# LB_BIT_i32_filter-v03_5_6.net
KiCad netlist of a schematic drawn in EAGLE
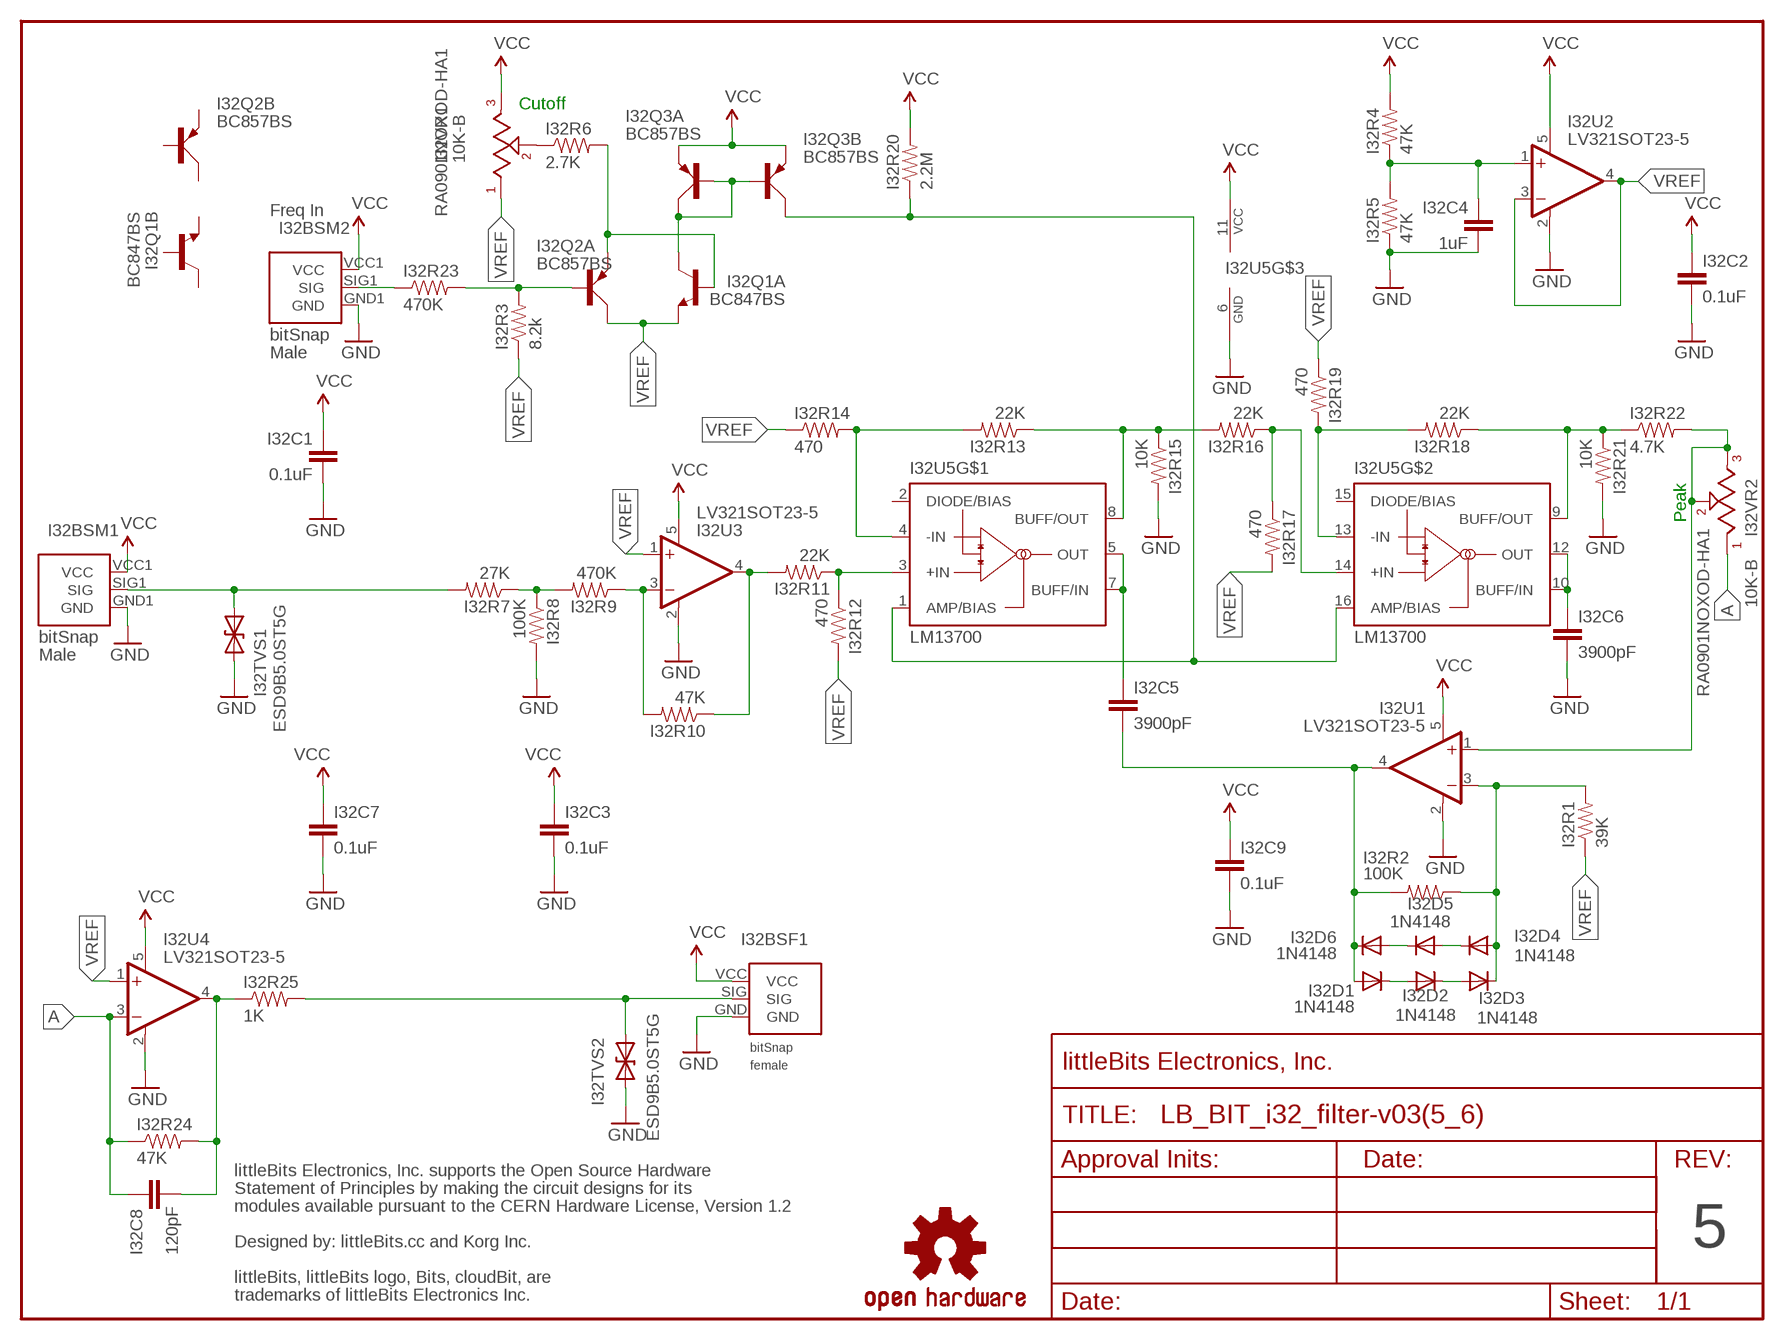
[diagram p0: schematic, sheet 1]

(export (version "E")
  (design (tool "Eeschema 10.0.6"))
  (components
    (comp (ref "I32BSF1")
      (value "BITSNAP_V03_FEMALE")
      (footprint "eagle-import:BITSNAP_V03_FEMALE")
      (libsource (lib "eagle-import") (part "BITSNAP_V03_FEMALE"))
    )
    (comp (ref "I32BSM1")
      (value "BITSNAP_V03_MALE")
      (footprint "eagle-import:BITSNAP_V03_MALE")
      (libsource (lib "eagle-import") (part "BITSNAP_V03_MALE"))
    )
    (comp (ref "I32BSM2")
      (value "BITSNAP_V03_MALE")
      (footprint "eagle-import:BITSNAP_V03_MALE")
      (libsource (lib "eagle-import") (part "BITSNAP_V03_MALE"))
    )
    (comp (ref "I32C1")
      (value "0.1uF")
      (footprint "eagle-import:CAP-0603")
      (libsource (lib "eagle-import") (part "CAPCAP-0603"))
    )
    (comp (ref "I32C2")
      (value "0.1uF")
      (footprint "eagle-import:CAP-0603")
      (libsource (lib "eagle-import") (part "CAPCAP-0603"))
    )
    (comp (ref "I32C3")
      (value "0.1uF")
      (footprint "eagle-import:CAP-0603")
      (libsource (lib "eagle-import") (part "CAPCAP-0603"))
    )
    (comp (ref "I32C4")
      (value "1uF")
      (footprint "eagle-import:CAP-0603")
      (libsource (lib "eagle-import") (part "CAPCAP-0603"))
    )
    (comp (ref "I32C5")
      (value "3900pF")
      (footprint "eagle-import:CAP-0603")
      (libsource (lib "eagle-import") (part "CAPCAP-0603"))
    )
    (comp (ref "I32C6")
      (value "3900pF")
      (footprint "eagle-import:CAP-0603")
      (libsource (lib "eagle-import") (part "CAPCAP-0603"))
    )
    (comp (ref "I32C7")
      (value "0.1uF")
      (footprint "eagle-import:CAP-0603")
      (libsource (lib "eagle-import") (part "CAPCAP-0603"))
    )
    (comp (ref "I32C8")
      (value "120pF")
      (footprint "eagle-import:CAP-0603")
      (libsource (lib "eagle-import") (part "CAPCAP-0603"))
    )
    (comp (ref "I32C9")
      (value "0.1uF")
      (footprint "eagle-import:CAP-0603")
      (libsource (lib "eagle-import") (part "CAPCAP-0603"))
    )
    (comp (ref "I32D1")
      (value "1N4148")
      (footprint "eagle-import:SOD-323")
      (libsource (lib "eagle-import") (part "DIODESOD"))
    )
    (comp (ref "I32D2")
      (value "1N4148")
      (footprint "eagle-import:SOD-323")
      (libsource (lib "eagle-import") (part "DIODESOD"))
    )
    (comp (ref "I32D3")
      (value "1N4148")
      (footprint "eagle-import:SOD-323")
      (libsource (lib "eagle-import") (part "DIODESOD"))
    )
    (comp (ref "I32D4")
      (value "1N4148")
      (footprint "eagle-import:SOD-323")
      (libsource (lib "eagle-import") (part "DIODESOD"))
    )
    (comp (ref "I32D5")
      (value "1N4148")
      (footprint "eagle-import:SOD-323")
      (libsource (lib "eagle-import") (part "DIODESOD"))
    )
    (comp (ref "I32D6")
      (value "1N4148")
      (footprint "eagle-import:SOD-323")
      (libsource (lib "eagle-import") (part "DIODESOD"))
    )
    (comp (ref "I32Q1")
      (value "BC847BS")
      (footprint "eagle-import:SOT-363_PHILLIPS")
      (libsource (lib "eagle-import") (part "TRANS-BJT_NPN-DUAL-BC847BS"))
    )
    (comp (ref "I32Q2")
      (value "BC857BS")
      (footprint "eagle-import:SOT-363_PHILLIPS")
      (libsource (lib "eagle-import") (part "TRANS-BJT_PNP-DUALBC857"))
    )
    (comp (ref "I32Q3")
      (value "BC857BS")
      (footprint "eagle-import:SOT-363_PHILLIPS")
      (libsource (lib "eagle-import") (part "TRANS-BJT_PNP-DUALBC857"))
    )
    (comp (ref "I32R1")
      (value "39K")
      (footprint "eagle-import:RES-0603")
      (libsource (lib "eagle-import") (part "RESISTOR0603"))
    )
    (comp (ref "I32R2")
      (value "100K")
      (footprint "eagle-import:RES-0603")
      (libsource (lib "eagle-import") (part "RESISTOR0603"))
    )
    (comp (ref "I32R3")
      (value "8.2k")
      (footprint "eagle-import:RES-0603")
      (libsource (lib "eagle-import") (part "RESISTOR0603"))
    )
    (comp (ref "I32R4")
      (value "47K")
      (footprint "eagle-import:RES-0603")
      (libsource (lib "eagle-import") (part "RESISTOR0603"))
    )
    (comp (ref "I32R5")
      (value "47K")
      (footprint "eagle-import:RES-0603")
      (libsource (lib "eagle-import") (part "RESISTOR0603"))
    )
    (comp (ref "I32R6")
      (value "2.7K")
      (footprint "eagle-import:RES-0603")
      (libsource (lib "eagle-import") (part "RESISTOR0603"))
    )
    (comp (ref "I32R7")
      (value "27K")
      (footprint "eagle-import:RES-0603")
      (libsource (lib "eagle-import") (part "RESISTOR0603"))
    )
    (comp (ref "I32R8")
      (value "100K")
      (footprint "eagle-import:RES-0603")
      (libsource (lib "eagle-import") (part "RESISTOR0603"))
    )
    (comp (ref "I32R9")
      (value "470K")
      (footprint "eagle-import:RES-0603")
      (libsource (lib "eagle-import") (part "RESISTOR0603"))
    )
    (comp (ref "I32R10")
      (value "47K")
      (footprint "eagle-import:RES-0603")
      (libsource (lib "eagle-import") (part "RESISTOR0603"))
    )
    (comp (ref "I32R11")
      (value "22K")
      (footprint "eagle-import:RES-0603")
      (libsource (lib "eagle-import") (part "RESISTOR0603"))
    )
    (comp (ref "I32R12")
      (value "470")
      (footprint "eagle-import:RES-0603")
      (libsource (lib "eagle-import") (part "RESISTOR0603"))
    )
    (comp (ref "I32R13")
      (value "22K")
      (footprint "eagle-import:RES-0603")
      (libsource (lib "eagle-import") (part "RESISTOR0603"))
    )
    (comp (ref "I32R14")
      (value "470")
      (footprint "eagle-import:RES-0603")
      (libsource (lib "eagle-import") (part "RESISTOR0603"))
    )
    (comp (ref "I32R15")
      (value "10K")
      (footprint "eagle-import:RES-0603")
      (libsource (lib "eagle-import") (part "RESISTOR0603"))
    )
    (comp (ref "I32R16")
      (value "22K")
      (footprint "eagle-import:RES-0603")
      (libsource (lib "eagle-import") (part "RESISTOR0603"))
    )
    (comp (ref "I32R17")
      (value "470")
      (footprint "eagle-import:RES-0603")
      (libsource (lib "eagle-import") (part "RESISTOR0603"))
    )
    (comp (ref "I32R18")
      (value "22K")
      (footprint "eagle-import:RES-0603")
      (libsource (lib "eagle-import") (part "RESISTOR0603"))
    )
    (comp (ref "I32R19")
      (value "470")
      (footprint "eagle-import:RES-0603")
      (libsource (lib "eagle-import") (part "RESISTOR0603"))
    )
    (comp (ref "I32R20")
      (value "2.2M")
      (footprint "eagle-import:RES-0603")
      (libsource (lib "eagle-import") (part "RESISTOR0603"))
    )
    (comp (ref "I32R21")
      (value "10K")
      (footprint "eagle-import:RES-0603")
      (libsource (lib "eagle-import") (part "RESISTOR0603"))
    )
    (comp (ref "I32R22")
      (value "4.7K")
      (footprint "eagle-import:RES-0603")
      (libsource (lib "eagle-import") (part "RESISTOR0603"))
    )
    (comp (ref "I32R23")
      (value "470K")
      (footprint "eagle-import:RES-0603")
      (libsource (lib "eagle-import") (part "RESISTOR0603"))
    )
    (comp (ref "I32R24")
      (value "47K")
      (footprint "eagle-import:RES-0603")
      (libsource (lib "eagle-import") (part "RESISTOR0603"))
    )
    (comp (ref "I32R25")
      (value "1K")
      (footprint "eagle-import:RES-0603")
      (libsource (lib "eagle-import") (part "RESISTOR0603"))
    )
    (comp (ref "I32TVS1")
      (value "ESD9B5.0ST5G")
      (footprint "eagle-import:SOD-923")
      (libsource (lib "eagle-import") (part "DIODE-TVSSOD-923"))
    )
    (comp (ref "I32TVS2")
      (value "ESD9B5.0ST5G")
      (footprint "eagle-import:SOD-923")
      (libsource (lib "eagle-import") (part "DIODE-TVSSOD-923"))
    )
    (comp (ref "I32U1")
      (value "LV321SOT23-5")
      (footprint "eagle-import:SOT23-5")
      (libsource (lib "eagle-import") (part "LV321SOT23-5"))
    )
    (comp (ref "I32U2")
      (value "LV321SOT23-5")
      (footprint "eagle-import:SOT23-5")
      (libsource (lib "eagle-import") (part "LV321SOT23-5"))
    )
    (comp (ref "I32U3")
      (value "LV321SOT23-5")
      (footprint "eagle-import:SOT23-5")
      (libsource (lib "eagle-import") (part "LV321SOT23-5"))
    )
    (comp (ref "I32U4")
      (value "LV321SOT23-5")
      (footprint "eagle-import:SOT23-5")
      (libsource (lib "eagle-import") (part "LV321SOT23-5"))
    )
    (comp (ref "I32U5")
      (value "LM13700")
      (footprint "eagle-import:DMP16")
      (libsource (lib "eagle-import") (part "XX-13700DMP16"))
    )
    (comp (ref "I32VR1")
      (value "10K-B")
      (footprint "eagle-import:ALPS_POT")
      (libsource (lib "eagle-import") (part "ALPS_POTTH"))
    )
    (comp (ref "I32VR2")
      (value "10K-B")
      (footprint "eagle-import:ALPS_POT")
      (libsource (lib "eagle-import") (part "ALPS_POTTH"))
    )
    (comp (ref "U$1")
      (value "FRAME-LETTER-OHWOHW")
      (footprint "eagle-import:FABDWG01-OHW")
      (libsource (lib "eagle-import") (part "FRAME-LETTER-OHWOHW"))
    )
    (comp (ref "U$2")
      (value "OSHWCREDIT-KORG")
      (footprint "eagle-import:OSHWCREDIT-KORG")
      (libsource (lib "eagle-import") (part "OSHWCREDIT-KORG"))
    )
    (comp (ref "U$3")
      (value "OSHW-LOGOL")
      (footprint "eagle-import:OSHW-LOGO-L")
      (libsource (lib "eagle-import") (part "OSHW-LOGOL"))
    )
  )
  (nets
    (net (code "1") (name "A") (class "Default")
      (node (ref "I32C8") (pin "1") (pinfunction "1_1") (pintype "passive"))
      (node (ref "I32R24") (pin "1") (pinfunction "1_1") (pintype "passive"))
      (node (ref "I32U4") (pin "3") (pinfunction "-IN_3") (pintype "input"))
      (node (ref "I32VR2") (pin "1") (pinfunction "1_1") (pintype "passive"))
    )
    (net (code "2") (name "GND") (class "Default")
      (node (ref "I32BSF1") (pin "GND") (pinfunction "GND_GND") (pintype "bidirectional"))
      (node (ref "I32BSM1") (pin "GND1") (pinfunction "GND_GND1") (pintype "bidirectional"))
      (node (ref "I32BSM2") (pin "GND1") (pinfunction "GND_GND1") (pintype "bidirectional"))
      (node (ref "I32C1") (pin "2") (pinfunction "2_2") (pintype "passive"))
      (node (ref "I32C2") (pin "2") (pinfunction "2_2") (pintype "passive"))
      (node (ref "I32C3") (pin "2") (pinfunction "2_2") (pintype "passive"))
      (node (ref "I32C4") (pin "2") (pinfunction "2_2") (pintype "passive"))
      (node (ref "I32C6") (pin "2") (pinfunction "2_2") (pintype "passive"))
      (node (ref "I32C7") (pin "2") (pinfunction "2_2") (pintype "passive"))
      (node (ref "I32C9") (pin "2") (pinfunction "2_2") (pintype "passive"))
      (node (ref "I32R15") (pin "2") (pinfunction "2_2") (pintype "passive"))
      (node (ref "I32R21") (pin "2") (pinfunction "2_2") (pintype "passive"))
      (node (ref "I32R5") (pin "1") (pinfunction "1_1") (pintype "passive"))
      (node (ref "I32R8") (pin "2") (pinfunction "2_2") (pintype "passive"))
      (node (ref "I32TVS1") (pin "1") (pinfunction "A_1") (pintype "passive"))
      (node (ref "I32TVS2") (pin "1") (pinfunction "A_1") (pintype "passive"))
      (node (ref "I32U1") (pin "2") (pinfunction "V-_2") (pintype "power_in"))
      (node (ref "I32U2") (pin "2") (pinfunction "V-_2") (pintype "power_in"))
      (node (ref "I32U3") (pin "2") (pinfunction "V-_2") (pintype "power_in"))
      (node (ref "I32U4") (pin "2") (pinfunction "V-_2") (pintype "power_in"))
      (node (ref "I32U5") (pin "6") (pinfunction "GND_6") (pintype "power_in"))
    )
    (net (code "3") (name "Net-(I32BSM1-SIG)") (class "Default")
      (node (ref "I32BSM1") (pin "SIG1") (pinfunction "SIG_SIG1") (pintype "bidirectional"))
      (node (ref "I32R7") (pin "2") (pinfunction "2_2") (pintype "passive"))
      (node (ref "I32TVS1") (pin "2") (pinfunction "C_2") (pintype "passive"))
    )
    (net (code "4") (name "Net-(I32BSM2-SIG)") (class "Default")
      (node (ref "I32BSM2") (pin "SIG1") (pinfunction "SIG_SIG1") (pintype "bidirectional"))
      (node (ref "I32R23") (pin "1") (pinfunction "1_1") (pintype "passive"))
    )
    (net (code "5") (name "Net-(I32D1-A)") (class "Default")
      (node (ref "I32C5") (pin "2") (pinfunction "2_2") (pintype "passive"))
      (node (ref "I32D1") (pin "2") (pinfunction "A_2") (pintype "passive"))
      (node (ref "I32D6") (pin "1") (pinfunction "C_1") (pintype "passive"))
      (node (ref "I32R2") (pin "2") (pinfunction "2_2") (pintype "passive"))
      (node (ref "I32U1") (pin "4") (pinfunction "OUT_4") (pintype "output"))
    )
    (net (code "6") (name "Net-(I32D1-C)") (class "Default")
      (node (ref "I32D1") (pin "1") (pinfunction "C_1") (pintype "passive"))
      (node (ref "I32D2") (pin "2") (pinfunction "A_2") (pintype "passive"))
    )
    (net (code "7") (name "Net-(I32D2-C)") (class "Default")
      (node (ref "I32D2") (pin "1") (pinfunction "C_1") (pintype "passive"))
      (node (ref "I32D3") (pin "2") (pinfunction "A_2") (pintype "passive"))
    )
    (net (code "8") (name "Net-(I32D3-C)") (class "Default")
      (node (ref "I32D3") (pin "1") (pinfunction "C_1") (pintype "passive"))
      (node (ref "I32D4") (pin "2") (pinfunction "A_2") (pintype "passive"))
      (node (ref "I32R1") (pin "2") (pinfunction "2_2") (pintype "passive"))
      (node (ref "I32R2") (pin "1") (pinfunction "1_1") (pintype "passive"))
      (node (ref "I32U1") (pin "3") (pinfunction "-IN_3") (pintype "input"))
    )
    (net (code "9") (name "Net-(I32D4-C)") (class "Default")
      (node (ref "I32D4") (pin "1") (pinfunction "C_1") (pintype "passive"))
      (node (ref "I32D5") (pin "2") (pinfunction "A_2") (pintype "passive"))
    )
    (net (code "10") (name "Net-(I32D5-C)") (class "Default")
      (node (ref "I32D5") (pin "1") (pinfunction "C_1") (pintype "passive"))
      (node (ref "I32D6") (pin "2") (pinfunction "A_2") (pintype "passive"))
    )
    (net (code "11") (name "Net-(I32Q1A-B)") (class "Default")
      (node (ref "I32Q1") (pin "2") (pinfunction "B_2") (pintype "passive"))
      (node (ref "I32Q2") (pin "1") (pinfunction "E_1") (pintype "passive"))
      (node (ref "I32R6") (pin "2") (pinfunction "2_2") (pintype "passive"))
    )
    (net (code "12") (name "Net-(I32Q1A-C)") (class "Default")
      (node (ref "I32Q1") (pin "6") (pinfunction "C_6") (pintype "passive"))
      (node (ref "I32Q3") (pin "2") (pinfunction "B_2") (pintype "passive"))
      (node (ref "I32Q3") (pin "5") (pinfunction "B_5") (pintype "passive"))
      (node (ref "I32Q3") (pin "6") (pinfunction "C_6") (pintype "passive"))
    )
    (net (code "13") (name "Net-(I32Q2A-B)") (class "Default")
      (node (ref "I32Q2") (pin "2") (pinfunction "B_2") (pintype "passive"))
      (node (ref "I32R23") (pin "2") (pinfunction "2_2") (pintype "passive"))
      (node (ref "I32R3") (pin "2") (pinfunction "2_2") (pintype "passive"))
    )
    (net (code "14") (name "Net-(I32Q3B-C)") (class "Default")
      (node (ref "I32Q3") (pin "3") (pinfunction "C_3") (pintype "passive"))
      (node (ref "I32R20") (pin "1") (pinfunction "1_1") (pintype "passive"))
      (node (ref "I32U5") (pin "1") (pinfunction "AMP/BIAS_1") (pintype "passive"))
      (node (ref "I32U5") (pin "16") (pinfunction "AMP/BIAS_16") (pintype "passive"))
    )
    (net (code "15") (name "Net-(I32R6-Pad1)") (class "Default")
      (node (ref "I32R6") (pin "1") (pinfunction "1_1") (pintype "passive"))
      (node (ref "I32VR1") (pin "2") (pinfunction "2_2") (pintype "passive"))
    )
    (net (code "16") (name "Net-(I32R7-Pad1)") (class "Default")
      (node (ref "I32R7") (pin "1") (pinfunction "1_1") (pintype "passive"))
      (node (ref "I32R8") (pin "1") (pinfunction "1_1") (pintype "passive"))
      (node (ref "I32R9") (pin "2") (pinfunction "2_2") (pintype "passive"))
    )
    (net (code "17") (name "Net-(I32TVS2-C)") (class "Default")
      (node (ref "I32BSF1") (pin "SIG") (pinfunction "SIG_SIG") (pintype "bidirectional"))
      (node (ref "I32R25") (pin "2") (pinfunction "2_2") (pintype "passive"))
      (node (ref "I32TVS2") (pin "2") (pinfunction "C_2") (pintype "passive"))
    )
    (net (code "18") (name "Net-(I32U1-+IN)") (class "Default")
      (node (ref "I32R22") (pin "2") (pinfunction "2_2") (pintype "passive"))
      (node (ref "I32U1") (pin "1") (pinfunction "+IN_1") (pintype "input"))
      (node (ref "I32VR2") (pin "2") (pinfunction "2_2") (pintype "passive"))
      (node (ref "I32VR2") (pin "3") (pinfunction "3_3") (pintype "passive"))
    )
    (net (code "19") (name "Net-(I32U2-+IN)") (class "Default")
      (node (ref "I32C4") (pin "1") (pinfunction "1_1") (pintype "passive"))
      (node (ref "I32R4") (pin "1") (pinfunction "1_1") (pintype "passive"))
      (node (ref "I32R5") (pin "2") (pinfunction "2_2") (pintype "passive"))
      (node (ref "I32U2") (pin "1") (pinfunction "+IN_1") (pintype "input"))
    )
    (net (code "20") (name "Net-(I32U3--IN)") (class "Default")
      (node (ref "I32R10") (pin "2") (pinfunction "2_2") (pintype "passive"))
      (node (ref "I32R9") (pin "1") (pinfunction "1_1") (pintype "passive"))
      (node (ref "I32U3") (pin "3") (pinfunction "-IN_3") (pintype "input"))
    )
    (net (code "21") (name "Net-(I32U3-OUT)") (class "Default")
      (node (ref "I32R10") (pin "1") (pinfunction "1_1") (pintype "passive"))
      (node (ref "I32R11") (pin "2") (pinfunction "2_2") (pintype "passive"))
      (node (ref "I32U3") (pin "4") (pinfunction "OUT_4") (pintype "output"))
    )
    (net (code "22") (name "Net-(I32U4-OUT)") (class "Default")
      (node (ref "I32C8") (pin "2") (pinfunction "2_2") (pintype "passive"))
      (node (ref "I32R24") (pin "2") (pinfunction "2_2") (pintype "passive"))
      (node (ref "I32R25") (pin "1") (pinfunction "1_1") (pintype "passive"))
      (node (ref "I32U4") (pin "4") (pinfunction "OUT_4") (pintype "output"))
    )
    (net (code "23") (name "Net-(I32U5A-+IN)") (class "Default")
      (node (ref "I32R11") (pin "1") (pinfunction "1_1") (pintype "passive"))
      (node (ref "I32R12") (pin "1") (pinfunction "1_1") (pintype "passive"))
      (node (ref "I32U5") (pin "3") (pinfunction "+IN_3") (pintype "input"))
    )
    (net (code "24") (name "Net-(I32U5A--IN)") (class "Default")
      (node (ref "I32R13") (pin "2") (pinfunction "2_2") (pintype "passive"))
      (node (ref "I32R14") (pin "2") (pinfunction "2_2") (pintype "passive"))
      (node (ref "I32U5") (pin "4") (pinfunction "-IN_4") (pintype "input"))
    )
    (net (code "25") (name "Net-(I32U5A-BUFF{slash}IN)") (class "Default")
      (node (ref "I32C5") (pin "1") (pinfunction "1_1") (pintype "passive"))
      (node (ref "I32U5") (pin "5") (pinfunction "OUT_5") (pintype "output"))
      (node (ref "I32U5") (pin "7") (pinfunction "BUFF/IN_7") (pintype "input"))
    )
    (net (code "26") (name "Net-(I32U5A-BUFF{slash}OUT)") (class "Default")
      (node (ref "I32R13") (pin "1") (pinfunction "1_1") (pintype "passive"))
      (node (ref "I32R15") (pin "1") (pinfunction "1_1") (pintype "passive"))
      (node (ref "I32R16") (pin "2") (pinfunction "2_2") (pintype "passive"))
      (node (ref "I32U5") (pin "8") (pinfunction "BUFF/OUT_8") (pintype "output"))
    )
    (net (code "27") (name "Net-(I32U5B-+IN)") (class "Default")
      (node (ref "I32R16") (pin "1") (pinfunction "1_1") (pintype "passive"))
      (node (ref "I32R17") (pin "1") (pinfunction "1_1") (pintype "passive"))
      (node (ref "I32U5") (pin "14") (pinfunction "+IN_14") (pintype "input"))
    )
    (net (code "28") (name "Net-(I32U5B--IN)") (class "Default")
      (node (ref "I32R18") (pin "2") (pinfunction "2_2") (pintype "passive"))
      (node (ref "I32R19") (pin "2") (pinfunction "2_2") (pintype "passive"))
      (node (ref "I32U5") (pin "13") (pinfunction "-IN_13") (pintype "input"))
    )
    (net (code "29") (name "Net-(I32U5B-BUFF{slash}IN)") (class "Default")
      (node (ref "I32C6") (pin "1") (pinfunction "1_1") (pintype "passive"))
      (node (ref "I32U5") (pin "10") (pinfunction "BUFF/IN_10") (pintype "input"))
      (node (ref "I32U5") (pin "12") (pinfunction "OUT_12") (pintype "output"))
    )
    (net (code "30") (name "Net-(I32U5B-BUFF{slash}OUT)") (class "Default")
      (node (ref "I32R18") (pin "1") (pinfunction "1_1") (pintype "passive"))
      (node (ref "I32R21") (pin "1") (pinfunction "1_1") (pintype "passive"))
      (node (ref "I32R22") (pin "1") (pinfunction "1_1") (pintype "passive"))
      (node (ref "I32U5") (pin "9") (pinfunction "BUFF/OUT_9") (pintype "output"))
    )
    (net (code "31") (name "VCC") (class "Default")
      (node (ref "I32BSF1") (pin "VCC") (pinfunction "VCC_VCC") (pintype "bidirectional"))
      (node (ref "I32BSM1") (pin "VCC1") (pinfunction "VCC_VCC1") (pintype "bidirectional"))
      (node (ref "I32BSM2") (pin "VCC1") (pinfunction "VCC_VCC1") (pintype "bidirectional"))
      (node (ref "I32C1") (pin "1") (pinfunction "1_1") (pintype "passive"))
      (node (ref "I32C2") (pin "1") (pinfunction "1_1") (pintype "passive"))
      (node (ref "I32C3") (pin "1") (pinfunction "1_1") (pintype "passive"))
      (node (ref "I32C7") (pin "1") (pinfunction "1_1") (pintype "passive"))
      (node (ref "I32C9") (pin "1") (pinfunction "1_1") (pintype "passive"))
      (node (ref "I32Q3") (pin "1") (pinfunction "E_1") (pintype "passive"))
      (node (ref "I32Q3") (pin "4") (pinfunction "E_4") (pintype "passive"))
      (node (ref "I32R20") (pin "2") (pinfunction "2_2") (pintype "passive"))
      (node (ref "I32R4") (pin "2") (pinfunction "2_2") (pintype "passive"))
      (node (ref "I32U1") (pin "5") (pinfunction "V+_5") (pintype "power_in"))
      (node (ref "I32U2") (pin "5") (pinfunction "V+_5") (pintype "power_in"))
      (node (ref "I32U3") (pin "5") (pinfunction "V+_5") (pintype "power_in"))
      (node (ref "I32U4") (pin "5") (pinfunction "V+_5") (pintype "power_in"))
      (node (ref "I32U5") (pin "11") (pinfunction "VCC_11") (pintype "power_in"))
      (node (ref "I32VR1") (pin "3") (pinfunction "3_3") (pintype "passive"))
    )
    (net (code "32") (name "VREF") (class "Default")
      (node (ref "I32Q1") (pin "1") (pinfunction "E_1") (pintype "passive"))
      (node (ref "I32Q2") (pin "6") (pinfunction "C_6") (pintype "passive"))
      (node (ref "I32R1") (pin "1") (pinfunction "1_1") (pintype "passive"))
      (node (ref "I32R12") (pin "2") (pinfunction "2_2") (pintype "passive"))
      (node (ref "I32R14") (pin "1") (pinfunction "1_1") (pintype "passive"))
      (node (ref "I32R17") (pin "2") (pinfunction "2_2") (pintype "passive"))
      (node (ref "I32R19") (pin "1") (pinfunction "1_1") (pintype "passive"))
      (node (ref "I32R3") (pin "1") (pinfunction "1_1") (pintype "passive"))
      (node (ref "I32U2") (pin "3") (pinfunction "-IN_3") (pintype "input"))
      (node (ref "I32U2") (pin "4") (pinfunction "OUT_4") (pintype "output"))
      (node (ref "I32U3") (pin "1") (pinfunction "+IN_1") (pintype "input"))
      (node (ref "I32U4") (pin "1") (pinfunction "+IN_1") (pintype "input"))
      (node (ref "I32VR1") (pin "1") (pinfunction "1_1") (pintype "passive"))
    )
    (net (code "33") (name "unconnected-(I32Q1B-B-Pad5)") (class "Default")
      (node (ref "I32Q1") (pin "5") (pinfunction "B_5") (pintype "passive"))
    )
    (net (code "34") (name "unconnected-(I32Q1B-C-Pad3)") (class "Default")
      (node (ref "I32Q1") (pin "3") (pinfunction "C_3") (pintype "passive"))
    )
    (net (code "35") (name "unconnected-(I32Q1B-E-Pad4)") (class "Default")
      (node (ref "I32Q1") (pin "4") (pinfunction "E_4") (pintype "passive"))
    )
    (net (code "36") (name "unconnected-(I32Q2B-B-Pad5)") (class "Default")
      (node (ref "I32Q2") (pin "5") (pinfunction "B_5") (pintype "passive"))
    )
    (net (code "37") (name "unconnected-(I32Q2B-C-Pad3)") (class "Default")
      (node (ref "I32Q2") (pin "3") (pinfunction "C_3") (pintype "passive"))
    )
    (net (code "38") (name "unconnected-(I32Q2B-E-Pad4)") (class "Default")
      (node (ref "I32Q2") (pin "4") (pinfunction "E_4") (pintype "passive"))
    )
    (net (code "39") (name "unconnected-(I32U5A-DIODE{slash}BIAS-Pad2)") (class "Default")
      (node (ref "I32U5") (pin "2") (pinfunction "DIODE/BIAS_2") (pintype "passive"))
    )
    (net (code "40") (name "unconnected-(I32U5B-DIODE{slash}BIAS-Pad15)") (class "Default")
      (node (ref "I32U5") (pin "15") (pinfunction "DIODE/BIAS_15") (pintype "passive"))
    )
  )
)
